# S205X.net
KiCad netlist of a schematic drawn in EAGLE
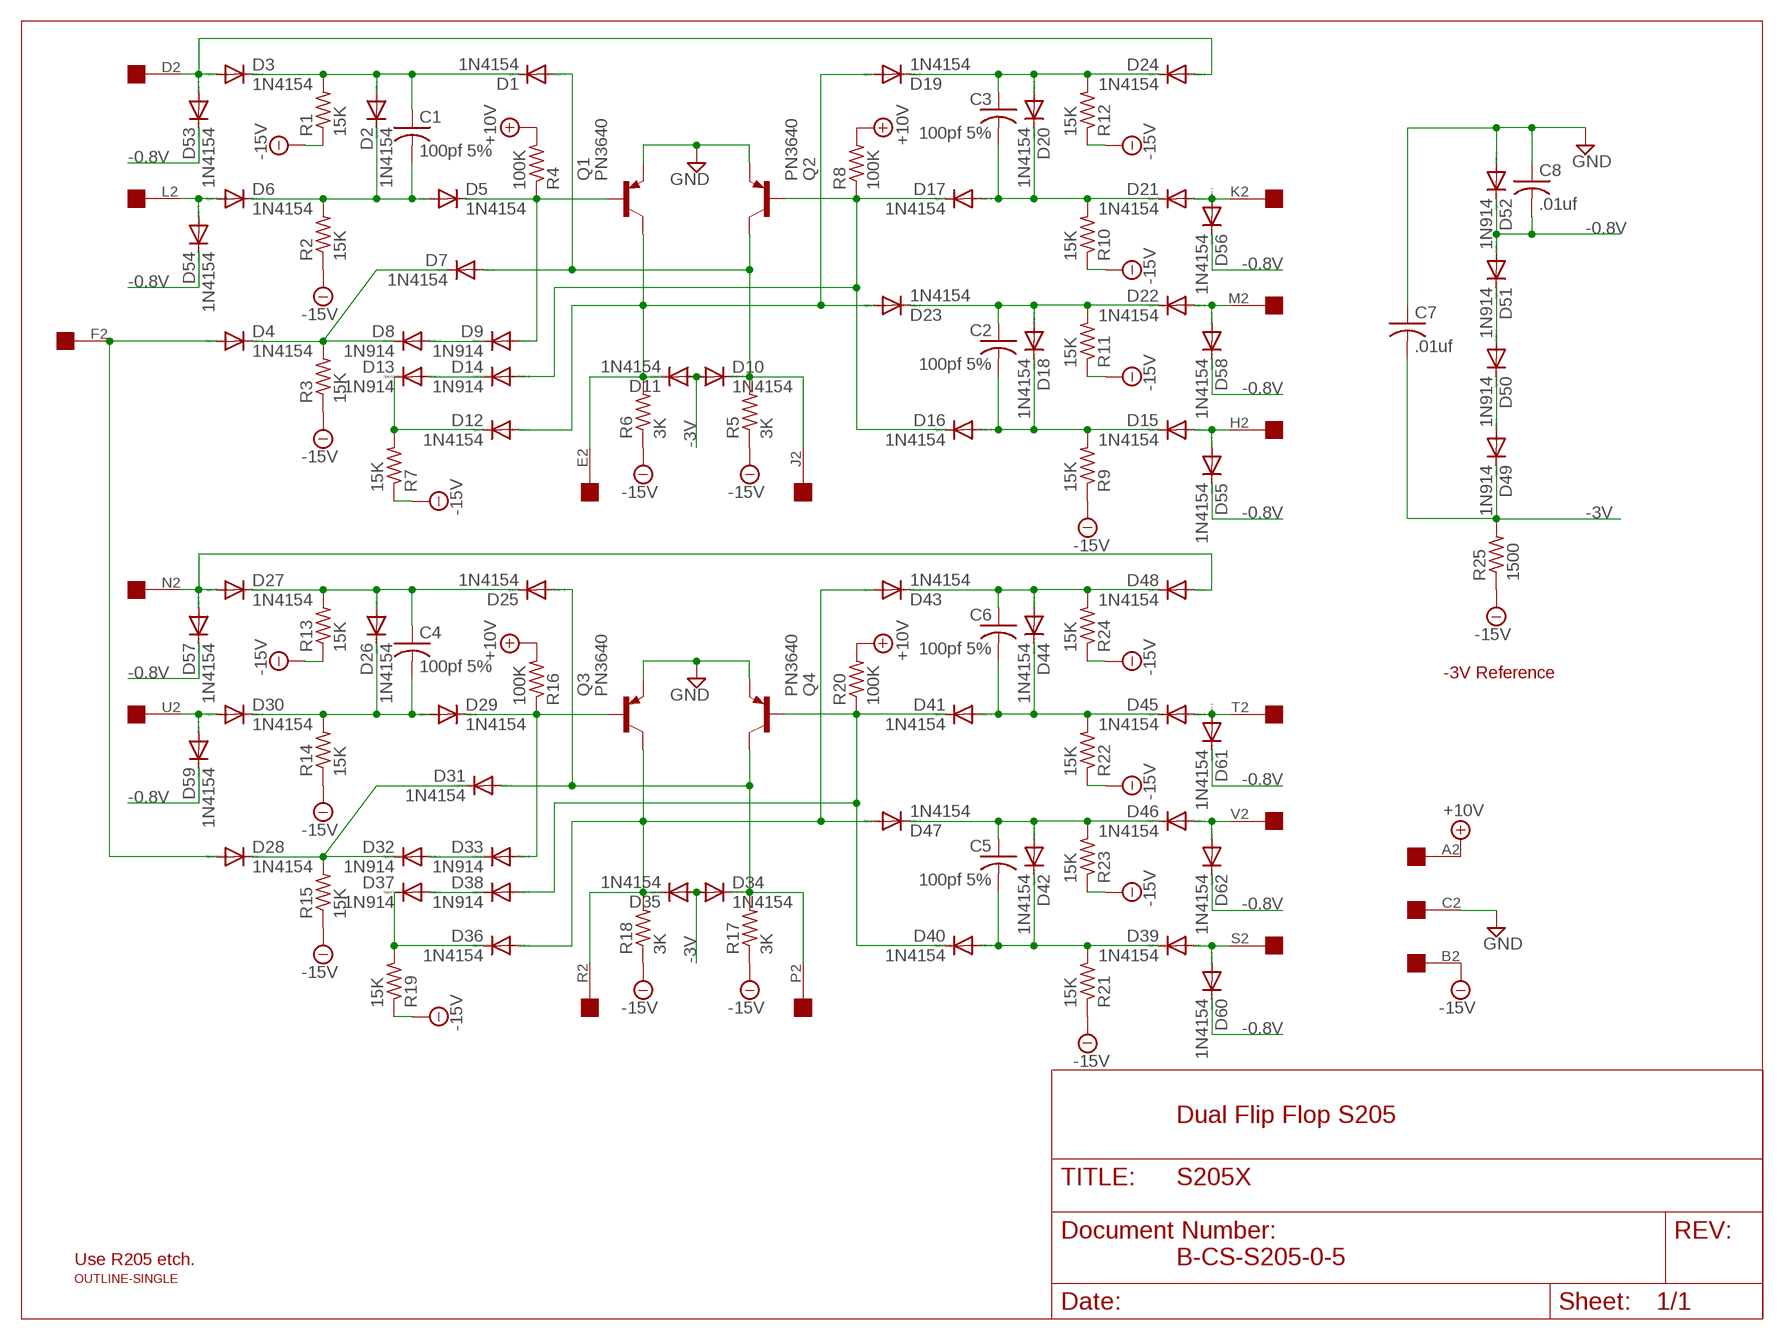
[diagram p0: schematic, sheet 1]

(export (version "E")
  (design (tool "Eeschema 10.0.6"))
  (components
    (comp (ref "C1")
      (value "100pf 5%")
      (footprint "eagle-import:C050-025X075")
      (libsource (lib "eagle-import") (part "C-US050-025X075"))
    )
    (comp (ref "C2")
      (value "100pf 5%")
      (footprint "eagle-import:C050-025X075")
      (libsource (lib "eagle-import") (part "C-US050-025X075"))
    )
    (comp (ref "C3")
      (value "100pf 5%")
      (footprint "eagle-import:C050-025X075")
      (libsource (lib "eagle-import") (part "C-US050-025X075"))
    )
    (comp (ref "C4")
      (value "100pf 5%")
      (footprint "eagle-import:C050-025X075")
      (libsource (lib "eagle-import") (part "C-US050-025X075"))
    )
    (comp (ref "C5")
      (value "100pf 5%")
      (footprint "eagle-import:C050-025X075")
      (libsource (lib "eagle-import") (part "C-US050-025X075"))
    )
    (comp (ref "C6")
      (value "100pf 5%")
      (footprint "eagle-import:C050-025X075")
      (libsource (lib "eagle-import") (part "C-US050-025X075"))
    )
    (comp (ref "C7")
      (value ".01uf")
      (footprint "eagle-import:C050-025X075")
      (libsource (lib "eagle-import") (part "C-US050-025X075"))
    )
    (comp (ref "C8")
      (value ".01uf")
      (footprint "eagle-import:C050-025X075")
      (libsource (lib "eagle-import") (part "C-US050-025X075"))
    )
    (comp (ref "D1")
      (value "1N4154")
      (footprint "eagle-import:DO35-10")
      (libsource (lib "eagle-import") (part "1N4148DO35-10"))
    )
    (comp (ref "D2")
      (value "1N4154")
      (footprint "eagle-import:DO35-10")
      (libsource (lib "eagle-import") (part "1N4148DO35-10"))
    )
    (comp (ref "D3")
      (value "1N4154")
      (footprint "eagle-import:DO35-10")
      (libsource (lib "eagle-import") (part "1N4148DO35-10"))
    )
    (comp (ref "D4")
      (value "1N4154")
      (footprint "eagle-import:DO35-10")
      (libsource (lib "eagle-import") (part "1N4148DO35-10"))
    )
    (comp (ref "D5")
      (value "1N4154")
      (footprint "eagle-import:DO35-10")
      (libsource (lib "eagle-import") (part "1N4148DO35-10"))
    )
    (comp (ref "D6")
      (value "1N4154")
      (footprint "eagle-import:DO35-10")
      (libsource (lib "eagle-import") (part "1N4148DO35-10"))
    )
    (comp (ref "D7")
      (value "1N4154")
      (footprint "eagle-import:DO35-10")
      (libsource (lib "eagle-import") (part "1N4148DO35-10"))
    )
    (comp (ref "D8")
      (value "1N914")
      (footprint "eagle-import:DO35-10")
      (libsource (lib "eagle-import") (part "1N4148DO35-10"))
    )
    (comp (ref "D9")
      (value "1N914")
      (footprint "eagle-import:DO35-10")
      (libsource (lib "eagle-import") (part "1N4148DO35-10"))
    )
    (comp (ref "D10")
      (value "1N4154")
      (footprint "eagle-import:DO35-10")
      (libsource (lib "eagle-import") (part "1N4148DO35-10"))
    )
    (comp (ref "D11")
      (value "1N4154")
      (footprint "eagle-import:DO35-10")
      (libsource (lib "eagle-import") (part "1N4148DO35-10"))
    )
    (comp (ref "D12")
      (value "1N4154")
      (footprint "eagle-import:DO35-10")
      (libsource (lib "eagle-import") (part "1N4148DO35-10"))
    )
    (comp (ref "D13")
      (value "1N914")
      (footprint "eagle-import:DO35-10")
      (libsource (lib "eagle-import") (part "1N4148DO35-10"))
    )
    (comp (ref "D14")
      (value "1N914")
      (footprint "eagle-import:DO35-10")
      (libsource (lib "eagle-import") (part "1N4148DO35-10"))
    )
    (comp (ref "D15")
      (value "1N4154")
      (footprint "eagle-import:DO35-10")
      (libsource (lib "eagle-import") (part "1N4148DO35-10"))
    )
    (comp (ref "D16")
      (value "1N4154")
      (footprint "eagle-import:DO35-10")
      (libsource (lib "eagle-import") (part "1N4148DO35-10"))
    )
    (comp (ref "D17")
      (value "1N4154")
      (footprint "eagle-import:DO35-10")
      (libsource (lib "eagle-import") (part "1N4148DO35-10"))
    )
    (comp (ref "D18")
      (value "1N4154")
      (footprint "eagle-import:DO35-10")
      (libsource (lib "eagle-import") (part "1N4148DO35-10"))
    )
    (comp (ref "D19")
      (value "1N4154")
      (footprint "eagle-import:DO35-10")
      (libsource (lib "eagle-import") (part "1N4148DO35-10"))
    )
    (comp (ref "D20")
      (value "1N4154")
      (footprint "eagle-import:DO35-10")
      (libsource (lib "eagle-import") (part "1N4148DO35-10"))
    )
    (comp (ref "D21")
      (value "1N4154")
      (footprint "eagle-import:DO35-10")
      (libsource (lib "eagle-import") (part "1N4148DO35-10"))
    )
    (comp (ref "D22")
      (value "1N4154")
      (footprint "eagle-import:DO35-10")
      (libsource (lib "eagle-import") (part "1N4148DO35-10"))
    )
    (comp (ref "D23")
      (value "1N4154")
      (footprint "eagle-import:DO35-10")
      (libsource (lib "eagle-import") (part "1N4148DO35-10"))
    )
    (comp (ref "D24")
      (value "1N4154")
      (footprint "eagle-import:DO35-10")
      (libsource (lib "eagle-import") (part "1N4148DO35-10"))
    )
    (comp (ref "D25")
      (value "1N4154")
      (footprint "eagle-import:DO35-10")
      (libsource (lib "eagle-import") (part "1N4148DO35-10"))
    )
    (comp (ref "D26")
      (value "1N4154")
      (footprint "eagle-import:DO35-10")
      (libsource (lib "eagle-import") (part "1N4148DO35-10"))
    )
    (comp (ref "D27")
      (value "1N4154")
      (footprint "eagle-import:DO35-10")
      (libsource (lib "eagle-import") (part "1N4148DO35-10"))
    )
    (comp (ref "D28")
      (value "1N4154")
      (footprint "eagle-import:DO35-10")
      (libsource (lib "eagle-import") (part "1N4148DO35-10"))
    )
    (comp (ref "D29")
      (value "1N4154")
      (footprint "eagle-import:DO35-10")
      (libsource (lib "eagle-import") (part "1N4148DO35-10"))
    )
    (comp (ref "D30")
      (value "1N4154")
      (footprint "eagle-import:DO35-10")
      (libsource (lib "eagle-import") (part "1N4148DO35-10"))
    )
    (comp (ref "D31")
      (value "1N4154")
      (footprint "eagle-import:DO35-10")
      (libsource (lib "eagle-import") (part "1N4148DO35-10"))
    )
    (comp (ref "D32")
      (value "1N914")
      (footprint "eagle-import:DO35-10")
      (libsource (lib "eagle-import") (part "1N4148DO35-10"))
    )
    (comp (ref "D33")
      (value "1N914")
      (footprint "eagle-import:DO35-10")
      (libsource (lib "eagle-import") (part "1N4148DO35-10"))
    )
    (comp (ref "D34")
      (value "1N4154")
      (footprint "eagle-import:DO35-10")
      (libsource (lib "eagle-import") (part "1N4148DO35-10"))
    )
    (comp (ref "D35")
      (value "1N4154")
      (footprint "eagle-import:DO35-10")
      (libsource (lib "eagle-import") (part "1N4148DO35-10"))
    )
    (comp (ref "D36")
      (value "1N4154")
      (footprint "eagle-import:DO35-10")
      (libsource (lib "eagle-import") (part "1N4148DO35-10"))
    )
    (comp (ref "D37")
      (value "1N914")
      (footprint "eagle-import:DO35-10")
      (libsource (lib "eagle-import") (part "1N4148DO35-10"))
    )
    (comp (ref "D38")
      (value "1N914")
      (footprint "eagle-import:DO35-10")
      (libsource (lib "eagle-import") (part "1N4148DO35-10"))
    )
    (comp (ref "D39")
      (value "1N4154")
      (footprint "eagle-import:DO35-10")
      (libsource (lib "eagle-import") (part "1N4148DO35-10"))
    )
    (comp (ref "D40")
      (value "1N4154")
      (footprint "eagle-import:DO35-10")
      (libsource (lib "eagle-import") (part "1N4148DO35-10"))
    )
    (comp (ref "D41")
      (value "1N4154")
      (footprint "eagle-import:DO35-10")
      (libsource (lib "eagle-import") (part "1N4148DO35-10"))
    )
    (comp (ref "D42")
      (value "1N4154")
      (footprint "eagle-import:DO35-10")
      (libsource (lib "eagle-import") (part "1N4148DO35-10"))
    )
    (comp (ref "D43")
      (value "1N4154")
      (footprint "eagle-import:DO35-10")
      (libsource (lib "eagle-import") (part "1N4148DO35-10"))
    )
    (comp (ref "D44")
      (value "1N4154")
      (footprint "eagle-import:DO35-10")
      (libsource (lib "eagle-import") (part "1N4148DO35-10"))
    )
    (comp (ref "D45")
      (value "1N4154")
      (footprint "eagle-import:DO35-10")
      (libsource (lib "eagle-import") (part "1N4148DO35-10"))
    )
    (comp (ref "D46")
      (value "1N4154")
      (footprint "eagle-import:DO35-10")
      (libsource (lib "eagle-import") (part "1N4148DO35-10"))
    )
    (comp (ref "D47")
      (value "1N4154")
      (footprint "eagle-import:DO35-10")
      (libsource (lib "eagle-import") (part "1N4148DO35-10"))
    )
    (comp (ref "D48")
      (value "1N4154")
      (footprint "eagle-import:DO35-10")
      (libsource (lib "eagle-import") (part "1N4148DO35-10"))
    )
    (comp (ref "D49")
      (value "1N914")
      (footprint "eagle-import:DO35-10")
      (libsource (lib "eagle-import") (part "1N4148DO35-10"))
    )
    (comp (ref "D50")
      (value "1N914")
      (footprint "eagle-import:DO35-10")
      (libsource (lib "eagle-import") (part "1N4148DO35-10"))
    )
    (comp (ref "D51")
      (value "1N914")
      (footprint "eagle-import:DO35-10")
      (libsource (lib "eagle-import") (part "1N4148DO35-10"))
    )
    (comp (ref "D52")
      (value "1N914")
      (footprint "eagle-import:DO35-10")
      (libsource (lib "eagle-import") (part "1N4148DO35-10"))
    )
    (comp (ref "D53")
      (value "1N4154")
      (footprint "eagle-import:DO35-10")
      (libsource (lib "eagle-import") (part "1N4148DO35-10"))
    )
    (comp (ref "D54")
      (value "1N4154")
      (footprint "eagle-import:DO35-10")
      (libsource (lib "eagle-import") (part "1N4148DO35-10"))
    )
    (comp (ref "D55")
      (value "1N4154")
      (footprint "eagle-import:DO35-10")
      (libsource (lib "eagle-import") (part "1N4148DO35-10"))
    )
    (comp (ref "D56")
      (value "1N4154")
      (footprint "eagle-import:DO35-10")
      (libsource (lib "eagle-import") (part "1N4148DO35-10"))
    )
    (comp (ref "D57")
      (value "1N4154")
      (footprint "eagle-import:DO35-10")
      (libsource (lib "eagle-import") (part "1N4148DO35-10"))
    )
    (comp (ref "D58")
      (value "1N4154")
      (footprint "eagle-import:DO35-10")
      (libsource (lib "eagle-import") (part "1N4148DO35-10"))
    )
    (comp (ref "D59")
      (value "1N4154")
      (footprint "eagle-import:DO35-10")
      (libsource (lib "eagle-import") (part "1N4148DO35-10"))
    )
    (comp (ref "D60")
      (value "1N4154")
      (footprint "eagle-import:DO35-10")
      (libsource (lib "eagle-import") (part "1N4148DO35-10"))
    )
    (comp (ref "D61")
      (value "1N4154")
      (footprint "eagle-import:DO35-10")
      (libsource (lib "eagle-import") (part "1N4148DO35-10"))
    )
    (comp (ref "D62")
      (value "1N4154")
      (footprint "eagle-import:DO35-10")
      (libsource (lib "eagle-import") (part "1N4148DO35-10"))
    )
    (comp (ref "Q1")
      (value "PN3640")
      (footprint "eagle-import:TO39")
      (libsource (lib "eagle-import") (part "2N3637"))
    )
    (comp (ref "Q2")
      (value "PN3640")
      (footprint "eagle-import:TO39")
      (libsource (lib "eagle-import") (part "2N3637"))
    )
    (comp (ref "Q3")
      (value "PN3640")
      (footprint "eagle-import:TO39")
      (libsource (lib "eagle-import") (part "2N3637"))
    )
    (comp (ref "Q4")
      (value "PN3640")
      (footprint "eagle-import:TO39")
      (libsource (lib "eagle-import") (part "2N3637"))
    )
    (comp (ref "R1")
      (value "15K")
      (footprint "eagle-import:0207_10")
      (libsource (lib "eagle-import") (part "R-US_0207/10"))
    )
    (comp (ref "R2")
      (value "15K")
      (footprint "eagle-import:0207_10")
      (libsource (lib "eagle-import") (part "R-US_0207/10"))
    )
    (comp (ref "R3")
      (value "15K")
      (footprint "eagle-import:0207_10")
      (libsource (lib "eagle-import") (part "R-US_0207/10"))
    )
    (comp (ref "R4")
      (value "100K")
      (footprint "eagle-import:0207_10")
      (libsource (lib "eagle-import") (part "R-US_0207/10"))
    )
    (comp (ref "R5")
      (value "3K")
      (footprint "eagle-import:0207_10")
      (libsource (lib "eagle-import") (part "R-US_0207/10"))
    )
    (comp (ref "R6")
      (value "3K")
      (footprint "eagle-import:0207_10")
      (libsource (lib "eagle-import") (part "R-US_0207/10"))
    )
    (comp (ref "R7")
      (value "15K")
      (footprint "eagle-import:0207_10")
      (libsource (lib "eagle-import") (part "R-US_0207/10"))
    )
    (comp (ref "R8")
      (value "100K")
      (footprint "eagle-import:0207_10")
      (libsource (lib "eagle-import") (part "R-US_0207/10"))
    )
    (comp (ref "R9")
      (value "15K")
      (footprint "eagle-import:0207_10")
      (libsource (lib "eagle-import") (part "R-US_0207/10"))
    )
    (comp (ref "R10")
      (value "15K")
      (footprint "eagle-import:0207_10")
      (libsource (lib "eagle-import") (part "R-US_0207/10"))
    )
    (comp (ref "R11")
      (value "15K")
      (footprint "eagle-import:0207_10")
      (libsource (lib "eagle-import") (part "R-US_0207/10"))
    )
    (comp (ref "R12")
      (value "15K")
      (footprint "eagle-import:0207_10")
      (libsource (lib "eagle-import") (part "R-US_0207/10"))
    )
    (comp (ref "R13")
      (value "15K")
      (footprint "eagle-import:0207_10")
      (libsource (lib "eagle-import") (part "R-US_0207/10"))
    )
    (comp (ref "R14")
      (value "15K")
      (footprint "eagle-import:0207_10")
      (libsource (lib "eagle-import") (part "R-US_0207/10"))
    )
    (comp (ref "R15")
      (value "15K")
      (footprint "eagle-import:0207_10")
      (libsource (lib "eagle-import") (part "R-US_0207/10"))
    )
    (comp (ref "R16")
      (value "100K")
      (footprint "eagle-import:0207_10")
      (libsource (lib "eagle-import") (part "R-US_0207/10"))
    )
    (comp (ref "R17")
      (value "3K")
      (footprint "eagle-import:0207_10")
      (libsource (lib "eagle-import") (part "R-US_0207/10"))
    )
    (comp (ref "R18")
      (value "3K")
      (footprint "eagle-import:0207_10")
      (libsource (lib "eagle-import") (part "R-US_0207/10"))
    )
    (comp (ref "R19")
      (value "15K")
      (footprint "eagle-import:0207_10")
      (libsource (lib "eagle-import") (part "R-US_0207/10"))
    )
    (comp (ref "R20")
      (value "100K")
      (footprint "eagle-import:0207_10")
      (libsource (lib "eagle-import") (part "R-US_0207/10"))
    )
    (comp (ref "R21")
      (value "15K")
      (footprint "eagle-import:0207_10")
      (libsource (lib "eagle-import") (part "R-US_0207/10"))
    )
    (comp (ref "R22")
      (value "15K")
      (footprint "eagle-import:0207_10")
      (libsource (lib "eagle-import") (part "R-US_0207/10"))
    )
    (comp (ref "R23")
      (value "15K")
      (footprint "eagle-import:0207_10")
      (libsource (lib "eagle-import") (part "R-US_0207/10"))
    )
    (comp (ref "R24")
      (value "15K")
      (footprint "eagle-import:0207_10")
      (libsource (lib "eagle-import") (part "R-US_0207/10"))
    )
    (comp (ref "R25")
      (value "1500")
      (footprint "eagle-import:0207_10")
      (libsource (lib "eagle-import") (part "R-US_0207/10"))
    )
    (comp (ref "U$1")
      (value "OUTLINE-SINGLE")
      (footprint "eagle-import:SINGLE")
      (libsource (lib "eagle-import") (part "OUTLINE-SINGLE"))
    )
    (comp (ref "U$2")
      (value "EDGE-1")
      (footprint "eagle-import:EDGE-CON1")
      (libsource (lib "eagle-import") (part "EDGE-1"))
    )
  )
  (nets
    (net (code "1") (name "+10V") (class "Default")
      (node (ref "R16") (pin "2") (pinfunction "2_2") (pintype "passive"))
      (node (ref "R20") (pin "2") (pinfunction "2_2") (pintype "passive"))
      (node (ref "R4") (pin "2") (pinfunction "2_2") (pintype "passive"))
      (node (ref "R8") (pin "2") (pinfunction "2_2") (pintype "passive"))
      (node (ref "U$2") (pin "A2") (pinfunction "1_A2") (pintype "bidirectional"))
    )
    (net (code "2") (name "-15V") (class "Default")
      (node (ref "R1") (pin "1") (pinfunction "1_1") (pintype "passive"))
      (node (ref "R10") (pin "1") (pinfunction "1_1") (pintype "passive"))
      (node (ref "R11") (pin "1") (pinfunction "1_1") (pintype "passive"))
      (node (ref "R12") (pin "1") (pinfunction "1_1") (pintype "passive"))
      (node (ref "R13") (pin "1") (pinfunction "1_1") (pintype "passive"))
      (node (ref "R14") (pin "1") (pinfunction "1_1") (pintype "passive"))
      (node (ref "R15") (pin "1") (pinfunction "1_1") (pintype "passive"))
      (node (ref "R17") (pin "1") (pinfunction "1_1") (pintype "passive"))
      (node (ref "R18") (pin "1") (pinfunction "1_1") (pintype "passive"))
      (node (ref "R19") (pin "1") (pinfunction "1_1") (pintype "passive"))
      (node (ref "R2") (pin "1") (pinfunction "1_1") (pintype "passive"))
      (node (ref "R21") (pin "1") (pinfunction "1_1") (pintype "passive"))
      (node (ref "R22") (pin "1") (pinfunction "1_1") (pintype "passive"))
      (node (ref "R23") (pin "1") (pinfunction "1_1") (pintype "passive"))
      (node (ref "R24") (pin "1") (pinfunction "1_1") (pintype "passive"))
      (node (ref "R25") (pin "1") (pinfunction "1_1") (pintype "passive"))
      (node (ref "R3") (pin "1") (pinfunction "1_1") (pintype "passive"))
      (node (ref "R5") (pin "1") (pinfunction "1_1") (pintype "passive"))
      (node (ref "R6") (pin "1") (pinfunction "1_1") (pintype "passive"))
      (node (ref "R7") (pin "1") (pinfunction "1_1") (pintype "passive"))
      (node (ref "R9") (pin "1") (pinfunction "1_1") (pintype "passive"))
      (node (ref "U$2") (pin "B2") (pinfunction "1_B2") (pintype "bidirectional"))
    )
    (net (code "3") (name "/-0.8V") (class "Default")
      (node (ref "C8") (pin "2") (pinfunction "2_2") (pintype "passive"))
      (node (ref "D51") (pin "A") (pinfunction "A_A") (pintype "passive"))
      (node (ref "D52") (pin "C") (pinfunction "C_C") (pintype "passive"))
      (node (ref "D53") (pin "C") (pinfunction "C_C") (pintype "passive"))
      (node (ref "D54") (pin "C") (pinfunction "C_C") (pintype "passive"))
      (node (ref "D55") (pin "C") (pinfunction "C_C") (pintype "passive"))
      (node (ref "D56") (pin "C") (pinfunction "C_C") (pintype "passive"))
      (node (ref "D57") (pin "C") (pinfunction "C_C") (pintype "passive"))
      (node (ref "D58") (pin "C") (pinfunction "C_C") (pintype "passive"))
      (node (ref "D59") (pin "C") (pinfunction "C_C") (pintype "passive"))
      (node (ref "D60") (pin "C") (pinfunction "C_C") (pintype "passive"))
      (node (ref "D61") (pin "C") (pinfunction "C_C") (pintype "passive"))
      (node (ref "D62") (pin "C") (pinfunction "C_C") (pintype "passive"))
    )
    (net (code "4") (name "/-3V") (class "Default")
      (node (ref "C7") (pin "2") (pinfunction "2_2") (pintype "passive"))
      (node (ref "D10") (pin "A") (pinfunction "A_A") (pintype "passive"))
      (node (ref "D11") (pin "A") (pinfunction "A_A") (pintype "passive"))
      (node (ref "D34") (pin "A") (pinfunction "A_A") (pintype "passive"))
      (node (ref "D35") (pin "A") (pinfunction "A_A") (pintype "passive"))
      (node (ref "D49") (pin "C") (pinfunction "C_C") (pintype "passive"))
      (node (ref "R25") (pin "2") (pinfunction "2_2") (pintype "passive"))
    )
    (net (code "5") (name "GND") (class "Default")
      (node (ref "C7") (pin "1") (pinfunction "1_1") (pintype "passive"))
      (node (ref "C8") (pin "1") (pinfunction "1_1") (pintype "passive"))
      (node (ref "D52") (pin "A") (pinfunction "A_A") (pintype "passive"))
      (node (ref "Q1") (pin "1") (pinfunction "E_1") (pintype "passive"))
      (node (ref "Q2") (pin "1") (pinfunction "E_1") (pintype "passive"))
      (node (ref "Q3") (pin "1") (pinfunction "E_1") (pintype "passive"))
      (node (ref "Q4") (pin "1") (pinfunction "E_1") (pintype "passive"))
      (node (ref "U$2") (pin "C2") (pinfunction "1_C2") (pintype "bidirectional"))
    )
    (net (code "6") (name "Net-(C1-Pad1)") (class "Default")
      (node (ref "C1") (pin "1") (pinfunction "1_1") (pintype "passive"))
      (node (ref "D1") (pin "C") (pinfunction "C_C") (pintype "passive"))
      (node (ref "D2") (pin "A") (pinfunction "A_A") (pintype "passive"))
      (node (ref "D3") (pin "C") (pinfunction "C_C") (pintype "passive"))
      (node (ref "R1") (pin "2") (pinfunction "2_2") (pintype "passive"))
    )
    (net (code "7") (name "Net-(C1-Pad2)") (class "Default")
      (node (ref "C1") (pin "2") (pinfunction "2_2") (pintype "passive"))
      (node (ref "D2") (pin "C") (pinfunction "C_C") (pintype "passive"))
      (node (ref "D5") (pin "A") (pinfunction "A_A") (pintype "passive"))
      (node (ref "D6") (pin "C") (pinfunction "C_C") (pintype "passive"))
      (node (ref "R2") (pin "2") (pinfunction "2_2") (pintype "passive"))
    )
    (net (code "8") (name "Net-(C2-Pad1)") (class "Default")
      (node (ref "C2") (pin "1") (pinfunction "1_1") (pintype "passive"))
      (node (ref "D18") (pin "A") (pinfunction "A_A") (pintype "passive"))
      (node (ref "D22") (pin "C") (pinfunction "C_C") (pintype "passive"))
      (node (ref "D23") (pin "C") (pinfunction "C_C") (pintype "passive"))
      (node (ref "R11") (pin "2") (pinfunction "2_2") (pintype "passive"))
    )
    (net (code "9") (name "Net-(C2-Pad2)") (class "Default")
      (node (ref "C2") (pin "2") (pinfunction "2_2") (pintype "passive"))
      (node (ref "D15") (pin "C") (pinfunction "C_C") (pintype "passive"))
      (node (ref "D16") (pin "A") (pinfunction "A_A") (pintype "passive"))
      (node (ref "D18") (pin "C") (pinfunction "C_C") (pintype "passive"))
      (node (ref "R9") (pin "2") (pinfunction "2_2") (pintype "passive"))
    )
    (net (code "10") (name "Net-(C3-Pad1)") (class "Default")
      (node (ref "C3") (pin "1") (pinfunction "1_1") (pintype "passive"))
      (node (ref "D19") (pin "C") (pinfunction "C_C") (pintype "passive"))
      (node (ref "D20") (pin "A") (pinfunction "A_A") (pintype "passive"))
      (node (ref "D24") (pin "C") (pinfunction "C_C") (pintype "passive"))
      (node (ref "R12") (pin "2") (pinfunction "2_2") (pintype "passive"))
    )
    (net (code "11") (name "Net-(C3-Pad2)") (class "Default")
      (node (ref "C3") (pin "2") (pinfunction "2_2") (pintype "passive"))
      (node (ref "D17") (pin "A") (pinfunction "A_A") (pintype "passive"))
      (node (ref "D20") (pin "C") (pinfunction "C_C") (pintype "passive"))
      (node (ref "D21") (pin "C") (pinfunction "C_C") (pintype "passive"))
      (node (ref "R10") (pin "2") (pinfunction "2_2") (pintype "passive"))
    )
    (net (code "12") (name "Net-(C4-Pad1)") (class "Default")
      (node (ref "C4") (pin "1") (pinfunction "1_1") (pintype "passive"))
      (node (ref "D25") (pin "C") (pinfunction "C_C") (pintype "passive"))
      (node (ref "D26") (pin "A") (pinfunction "A_A") (pintype "passive"))
      (node (ref "D27") (pin "C") (pinfunction "C_C") (pintype "passive"))
      (node (ref "R13") (pin "2") (pinfunction "2_2") (pintype "passive"))
    )
    (net (code "13") (name "Net-(C4-Pad2)") (class "Default")
      (node (ref "C4") (pin "2") (pinfunction "2_2") (pintype "passive"))
      (node (ref "D26") (pin "C") (pinfunction "C_C") (pintype "passive"))
      (node (ref "D29") (pin "A") (pinfunction "A_A") (pintype "passive"))
      (node (ref "D30") (pin "C") (pinfunction "C_C") (pintype "passive"))
      (node (ref "R14") (pin "2") (pinfunction "2_2") (pintype "passive"))
    )
    (net (code "14") (name "Net-(C5-Pad1)") (class "Default")
      (node (ref "C5") (pin "1") (pinfunction "1_1") (pintype "passive"))
      (node (ref "D42") (pin "A") (pinfunction "A_A") (pintype "passive"))
      (node (ref "D46") (pin "C") (pinfunction "C_C") (pintype "passive"))
      (node (ref "D47") (pin "C") (pinfunction "C_C") (pintype "passive"))
      (node (ref "R23") (pin "2") (pinfunction "2_2") (pintype "passive"))
    )
    (net (code "15") (name "Net-(C5-Pad2)") (class "Default")
      (node (ref "C5") (pin "2") (pinfunction "2_2") (pintype "passive"))
      (node (ref "D39") (pin "C") (pinfunction "C_C") (pintype "passive"))
      (node (ref "D40") (pin "A") (pinfunction "A_A") (pintype "passive"))
      (node (ref "D42") (pin "C") (pinfunction "C_C") (pintype "passive"))
      (node (ref "R21") (pin "2") (pinfunction "2_2") (pintype "passive"))
    )
    (net (code "16") (name "Net-(C6-Pad1)") (class "Default")
      (node (ref "C6") (pin "1") (pinfunction "1_1") (pintype "passive"))
      (node (ref "D43") (pin "C") (pinfunction "C_C") (pintype "passive"))
      (node (ref "D44") (pin "A") (pinfunction "A_A") (pintype "passive"))
      (node (ref "D48") (pin "C") (pinfunction "C_C") (pintype "passive"))
      (node (ref "R24") (pin "2") (pinfunction "2_2") (pintype "passive"))
    )
    (net (code "17") (name "Net-(C6-Pad2)") (class "Default")
      (node (ref "C6") (pin "2") (pinfunction "2_2") (pintype "passive"))
      (node (ref "D41") (pin "A") (pinfunction "A_A") (pintype "passive"))
      (node (ref "D44") (pin "C") (pinfunction "C_C") (pintype "passive"))
      (node (ref "D45") (pin "C") (pinfunction "C_C") (pintype "passive"))
      (node (ref "R22") (pin "2") (pinfunction "2_2") (pintype "passive"))
    )
    (net (code "18") (name "Net-(D4-PadC)") (class "Default")
      (node (ref "D4") (pin "C") (pinfunction "C_C") (pintype "passive"))
      (node (ref "D7") (pin "C") (pinfunction "C_C") (pintype "passive"))
      (node (ref "D8") (pin "C") (pinfunction "C_C") (pintype "passive"))
      (node (ref "R3") (pin "2") (pinfunction "2_2") (pintype "passive"))
    )
    (net (code "19") (name "Net-(D8-PadA)") (class "Default")
      (node (ref "D8") (pin "A") (pinfunction "A_A") (pintype "passive"))
      (node (ref "D9") (pin "C") (pinfunction "C_C") (pintype "passive"))
    )
    (net (code "20") (name "Net-(D12-PadC)") (class "Default")
      (node (ref "D12") (pin "C") (pinfunction "C_C") (pintype "passive"))
      (node (ref "D13") (pin "C") (pinfunction "C_C") (pintype "passive"))
      (node (ref "R7") (pin "2") (pinfunction "2_2") (pintype "passive"))
    )
    (net (code "21") (name "Net-(D13-PadA)") (class "Default")
      (node (ref "D13") (pin "A") (pinfunction "A_A") (pintype "passive"))
      (node (ref "D14") (pin "C") (pinfunction "C_C") (pintype "passive"))
    )
    (net (code "22") (name "Net-(D28-PadC)") (class "Default")
      (node (ref "D28") (pin "C") (pinfunction "C_C") (pintype "passive"))
      (node (ref "D31") (pin "C") (pinfunction "C_C") (pintype "passive"))
      (node (ref "D32") (pin "C") (pinfunction "C_C") (pintype "passive"))
      (node (ref "R15") (pin "2") (pinfunction "2_2") (pintype "passive"))
    )
    (net (code "23") (name "Net-(D32-PadA)") (class "Default")
      (node (ref "D32") (pin "A") (pinfunction "A_A") (pintype "passive"))
      (node (ref "D33") (pin "C") (pinfunction "C_C") (pintype "passive"))
    )
    (net (code "24") (name "Net-(D36-PadC)") (class "Default")
      (node (ref "D36") (pin "C") (pinfunction "C_C") (pintype "passive"))
      (node (ref "D37") (pin "C") (pinfunction "C_C") (pintype "passive"))
      (node (ref "R19") (pin "2") (pinfunction "2_2") (pintype "passive"))
    )
    (net (code "25") (name "Net-(D37-PadA)") (class "Default")
      (node (ref "D37") (pin "A") (pinfunction "A_A") (pintype "passive"))
      (node (ref "D38") (pin "C") (pinfunction "C_C") (pintype "passive"))
    )
    (net (code "26") (name "Net-(D49-PadA)") (class "Default")
      (node (ref "D49") (pin "A") (pinfunction "A_A") (pintype "passive"))
      (node (ref "D50") (pin "C") (pinfunction "C_C") (pintype "passive"))
    )
    (net (code "27") (name "Net-(D50-PadA)") (class "Default")
      (node (ref "D50") (pin "A") (pinfunction "A_A") (pintype "passive"))
      (node (ref "D51") (pin "C") (pinfunction "C_C") (pintype "passive"))
    )
    (net (code "28") (name "Net-(Q1-B)") (class "Default")
      (node (ref "D5") (pin "C") (pinfunction "C_C") (pintype "passive"))
      (node (ref "D9") (pin "A") (pinfunction "A_A") (pintype "passive"))
      (node (ref "Q1") (pin "2") (pinfunction "B_2") (pintype "passive"))
      (node (ref "R4") (pin "1") (pinfunction "1_1") (pintype "passive"))
    )
    (net (code "29") (name "Net-(Q1-C)") (class "Default")
      (node (ref "D11") (pin "C") (pinfunction "C_C") (pintype "passive"))
      (node (ref "D12") (pin "A") (pinfunction "A_A") (pintype "passive"))
      (node (ref "D19") (pin "A") (pinfunction "A_A") (pintype "passive"))
      (node (ref "D23") (pin "A") (pinfunction "A_A") (pintype "passive"))
      (node (ref "Q1") (pin "3") (pinfunction "C_3") (pintype "passive"))
      (node (ref "R6") (pin "2") (pinfunction "2_2") (pintype "passive"))
      (node (ref "U$2") (pin "E2") (pinfunction "1_E2") (pintype "bidirectional"))
    )
    (net (code "30") (name "Net-(Q2-B)") (class "Default")
      (node (ref "D14") (pin "A") (pinfunction "A_A") (pintype "passive"))
      (node (ref "D16") (pin "C") (pinfunction "C_C") (pintype "passive"))
      (node (ref "D17") (pin "C") (pinfunction "C_C") (pintype "passive"))
      (node (ref "Q2") (pin "2") (pinfunction "B_2") (pintype "passive"))
      (node (ref "R8") (pin "1") (pinfunction "1_1") (pintype "passive"))
    )
    (net (code "31") (name "Net-(Q2-C)") (class "Default")
      (node (ref "D1") (pin "A") (pinfunction "A_A") (pintype "passive"))
      (node (ref "D10") (pin "C") (pinfunction "C_C") (pintype "passive"))
      (node (ref "D7") (pin "A") (pinfunction "A_A") (pintype "passive"))
      (node (ref "Q2") (pin "3") (pinfunction "C_3") (pintype "passive"))
      (node (ref "R5") (pin "2") (pinfunction "2_2") (pintype "passive"))
      (node (ref "U$2") (pin "J2") (pinfunction "1_J2") (pintype "bidirectional"))
    )
    (net (code "32") (name "Net-(Q3-B)") (class "Default")
      (node (ref "D29") (pin "C") (pinfunction "C_C") (pintype "passive"))
      (node (ref "D33") (pin "A") (pinfunction "A_A") (pintype "passive"))
      (node (ref "Q3") (pin "2") (pinfunction "B_2") (pintype "passive"))
      (node (ref "R16") (pin "1") (pinfunction "1_1") (pintype "passive"))
    )
    (net (code "33") (name "Net-(Q3-C)") (class "Default")
      (node (ref "D35") (pin "C") (pinfunction "C_C") (pintype "passive"))
      (node (ref "D36") (pin "A") (pinfunction "A_A") (pintype "passive"))
      (node (ref "D43") (pin "A") (pinfunction "A_A") (pintype "passive"))
      (node (ref "D47") (pin "A") (pinfunction "A_A") (pintype "passive"))
      (node (ref "Q3") (pin "3") (pinfunction "C_3") (pintype "passive"))
      (node (ref "R18") (pin "2") (pinfunction "2_2") (pintype "passive"))
      (node (ref "U$2") (pin "R2") (pinfunction "1_R2") (pintype "bidirectional"))
    )
    (net (code "34") (name "Net-(Q4-B)") (class "Default")
      (node (ref "D38") (pin "A") (pinfunction "A_A") (pintype "passive"))
      (node (ref "D40") (pin "C") (pinfunction "C_C") (pintype "passive"))
      (node (ref "D41") (pin "C") (pinfunction "C_C") (pintype "passive"))
      (node (ref "Q4") (pin "2") (pinfunction "B_2") (pintype "passive"))
      (node (ref "R20") (pin "1") (pinfunction "1_1") (pintype "passive"))
    )
    (net (code "35") (name "Net-(Q4-C)") (class "Default")
      (node (ref "D25") (pin "A") (pinfunction "A_A") (pintype "passive"))
      (node (ref "D31") (pin "A") (pinfunction "A_A") (pintype "passive"))
      (node (ref "D34") (pin "C") (pinfunction "C_C") (pintype "passive"))
      (node (ref "Q4") (pin "3") (pinfunction "C_3") (pintype "passive"))
      (node (ref "R17") (pin "2") (pinfunction "2_2") (pintype "passive"))
      (node (ref "U$2") (pin "P2") (pinfunction "1_P2") (pintype "bidirectional"))
    )
    (net (code "36") (name "Net-(U$2D-1)") (class "Default")
      (node (ref "D24") (pin "A") (pinfunction "A_A") (pintype "passive"))
      (node (ref "D3") (pin "A") (pinfunction "A_A") (pintype "passive"))
      (node (ref "D53") (pin "A") (pinfunction "A_A") (pintype "passive"))
      (node (ref "U$2") (pin "D2") (pinfunction "1_D2") (pintype "bidirectional"))
    )
    (net (code "37") (name "Net-(U$2F-1)") (class "Default")
      (node (ref "D28") (pin "A") (pinfunction "A_A") (pintype "passive"))
      (node (ref "D4") (pin "A") (pinfunction "A_A") (pintype "passive"))
      (node (ref "U$2") (pin "F2") (pinfunction "1_F2") (pintype "bidirectional"))
    )
    (net (code "38") (name "Net-(U$2G-1)") (class "Default")
      (node (ref "D15") (pin "A") (pinfunction "A_A") (pintype "passive"))
      (node (ref "D55") (pin "A") (pinfunction "A_A") (pintype "passive"))
      (node (ref "U$2") (pin "H2") (pinfunction "1_H2") (pintype "bidirectional"))
    )
    (net (code "39") (name "Net-(U$2I-1)") (class "Default")
      (node (ref "D21") (pin "A") (pinfunction "A_A") (pintype "passive"))
      (node (ref "D56") (pin "A") (pinfunction "A_A") (pintype "passive"))
      (node (ref "U$2") (pin "K2") (pinfunction "1_K2") (pintype "bidirectional"))
    )
    (net (code "40") (name "Net-(U$2J-1)") (class "Default")
      (node (ref "D54") (pin "A") (pinfunction "A_A") (pintype "passive"))
      (node (ref "D6") (pin "A") (pinfunction "A_A") (pintype "passive"))
      (node (ref "U$2") (pin "L2") (pinfunction "1_L2") (pintype "bidirectional"))
    )
    (net (code "41") (name "Net-(U$2K-1)") (class "Default")
      (node (ref "D22") (pin "A") (pinfunction "A_A") (pintype "passive"))
      (node (ref "D58") (pin "A") (pinfunction "A_A") (pintype "passive"))
      (node (ref "U$2") (pin "M2") (pinfunction "1_M2") (pintype "bidirectional"))
    )
    (net (code "42") (name "Net-(U$2L-1)") (class "Default")
      (node (ref "D27") (pin "A") (pinfunction "A_A") (pintype "passive"))
      (node (ref "D48") (pin "A") (pinfunction "A_A") (pintype "passive"))
      (node (ref "D57") (pin "A") (pinfunction "A_A") (pintype "passive"))
      (node (ref "U$2") (pin "N2") (pinfunction "1_N2") (pintype "bidirectional"))
    )
    (net (code "43") (name "Net-(U$2O-1)") (class "Default")
      (node (ref "D39") (pin "A") (pinfunction "A_A") (pintype "passive"))
      (node (ref "D60") (pin "A") (pinfunction "A_A") (pintype "passive"))
      (node (ref "U$2") (pin "S2") (pinfunction "1_S2") (pintype "bidirectional"))
    )
    (net (code "44") (name "Net-(U$2P-1)") (class "Default")
      (node (ref "D45") (pin "A") (pinfunction "A_A") (pintype "passive"))
      (node (ref "D61") (pin "A") (pinfunction "A_A") (pintype "passive"))
      (node (ref "U$2") (pin "T2") (pinfunction "1_T2") (pintype "bidirectional"))
    )
    (net (code "45") (name "Net-(U$2Q-1)") (class "Default")
      (node (ref "D30") (pin "A") (pinfunction "A_A") (pintype "passive"))
      (node (ref "D59") (pin "A") (pinfunction "A_A") (pintype "passive"))
      (node (ref "U$2") (pin "U2") (pinfunction "1_U2") (pintype "bidirectional"))
    )
    (net (code "46") (name "Net-(U$2R-1)") (class "Default")
      (node (ref "D46") (pin "A") (pinfunction "A_A") (pintype "passive"))
      (node (ref "D62") (pin "A") (pinfunction "A_A") (pintype "passive"))
      (node (ref "U$2") (pin "V2") (pinfunction "1_V2") (pintype "bidirectional"))
    )
  )
)
